# encoder_wrist.net
KiCad netlist of a schematic drawn in EAGLE
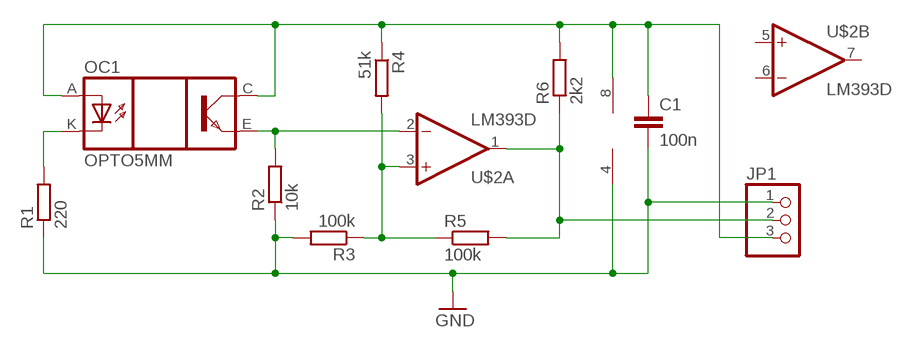
[diagram p0: schematic, sheet 1]

(export (version "E")
  (design (tool "Eeschema 10.0.6"))
  (components
    (comp (ref "C1")
      (value "100n")
      (footprint "eagle-import:C1206")
      (libsource (lib "eagle-import") (part "C-EUC1206"))
    )
    (comp (ref "JP1")
      (value "PINHD-1X3/90")
      (footprint "eagle-import:1X03_90")
      (libsource (lib "eagle-import") (part "PINHD-1X3/90"))
    )
    (comp (ref "OC1")
      (value "OPTO5MM")
      (footprint "eagle-import:OPTO_5MM")
      (libsource (lib "eagle-import") (part "OPTO5MM"))
    )
    (comp (ref "R1")
      (value "220")
      (footprint "eagle-import:M1206")
      (libsource (lib "eagle-import") (part "R-EU_M1206"))
    )
    (comp (ref "R2")
      (value "10k")
      (footprint "eagle-import:M1206")
      (libsource (lib "eagle-import") (part "R-EU_M1206"))
    )
    (comp (ref "R3")
      (value "100k")
      (footprint "eagle-import:M1206")
      (libsource (lib "eagle-import") (part "R-EU_M1206"))
    )
    (comp (ref "R4")
      (value "51k")
      (footprint "eagle-import:M1206")
      (libsource (lib "eagle-import") (part "R-EU_M1206"))
    )
    (comp (ref "R5")
      (value "100k")
      (footprint "eagle-import:M1206")
      (libsource (lib "eagle-import") (part "R-EU_M1206"))
    )
    (comp (ref "R6")
      (value "2k2")
      (footprint "eagle-import:M1206")
      (libsource (lib "eagle-import") (part "R-EU_M1206"))
    )
    (comp (ref "U$2")
      (value "LM393D")
      (footprint "eagle-import:SO08")
      (libsource (lib "eagle-import") (part "LM393D"))
    )
  )
  (nets
    (net (code "1") (name "GND") (class "Default")
      (node (ref "C1") (pin "2") (pinfunction "2_2") (pintype "passive"))
      (node (ref "JP1") (pin "1") (pinfunction "1_1") (pintype "passive"))
      (node (ref "R1") (pin "1") (pinfunction "1_1") (pintype "passive"))
      (node (ref "R2") (pin "1") (pinfunction "1_1") (pintype "passive"))
      (node (ref "R3") (pin "2") (pinfunction "2_2") (pintype "passive"))
      (node (ref "U$2") (pin "4") (pinfunction "V-_4") (pintype "power_in"))
    )
    (net (code "2") (name "Net-(OC1-C)") (class "Default")
      (node (ref "OC1") (pin "K") (pinfunction "C_K") (pintype "passive"))
      (node (ref "R1") (pin "2") (pinfunction "2_2") (pintype "passive"))
    )
    (net (code "3") (name "Net-(OC1-COL)") (class "Default")
      (node (ref "C1") (pin "1") (pinfunction "1_1") (pintype "passive"))
      (node (ref "JP1") (pin "3") (pinfunction "3_3") (pintype "passive"))
      (node (ref "OC1") (pin "A") (pinfunction "A_A") (pintype "passive"))
      (node (ref "OC1") (pin "C") (pinfunction "COL_C") (pintype "passive"))
      (node (ref "R4") (pin "1") (pinfunction "1_1") (pintype "passive"))
      (node (ref "R6") (pin "2") (pinfunction "2_2") (pintype "passive"))
      (node (ref "U$2") (pin "8") (pinfunction "V+_8") (pintype "power_in"))
    )
    (net (code "4") (name "Net-(OC1-EMIT)") (class "Default")
      (node (ref "OC1") (pin "E") (pinfunction "EMIT_E") (pintype "passive"))
      (node (ref "R2") (pin "2") (pinfunction "2_2") (pintype "passive"))
      (node (ref "U$2") (pin "2") (pinfunction "-IN_2") (pintype "input"))
    )
    (net (code "5") (name "Net-(U$2A-+IN)") (class "Default")
      (node (ref "R3") (pin "1") (pinfunction "1_1") (pintype "passive"))
      (node (ref "R4") (pin "2") (pinfunction "2_2") (pintype "passive"))
      (node (ref "R5") (pin "1") (pinfunction "1_1") (pintype "passive"))
      (node (ref "U$2") (pin "3") (pinfunction "+IN_3") (pintype "input"))
    )
    (net (code "6") (name "Net-(U$2A-OUT)") (class "Default")
      (node (ref "JP1") (pin "2") (pinfunction "2_2") (pintype "passive"))
      (node (ref "R5") (pin "2") (pinfunction "2_2") (pintype "passive"))
      (node (ref "R6") (pin "1") (pinfunction "1_1") (pintype "passive"))
      (node (ref "U$2") (pin "1") (pinfunction "OUT_1") (pintype "output"))
    )
    (net (code "7") (name "unconnected-(U$2B-+IN-Pad5)") (class "Default")
      (node (ref "U$2") (pin "5") (pinfunction "+IN_5") (pintype "input"))
    )
    (net (code "8") (name "unconnected-(U$2B--IN-Pad6)") (class "Default")
      (node (ref "U$2") (pin "6") (pinfunction "-IN_6") (pintype "input"))
    )
    (net (code "9") (name "unconnected-(U$2B-OUT-Pad7)") (class "Default")
      (node (ref "U$2") (pin "7") (pinfunction "OUT_7") (pintype "output"))
    )
  )
)
